# pa-2g.net
KiCad netlist of a schematic drawn in Altium Designer
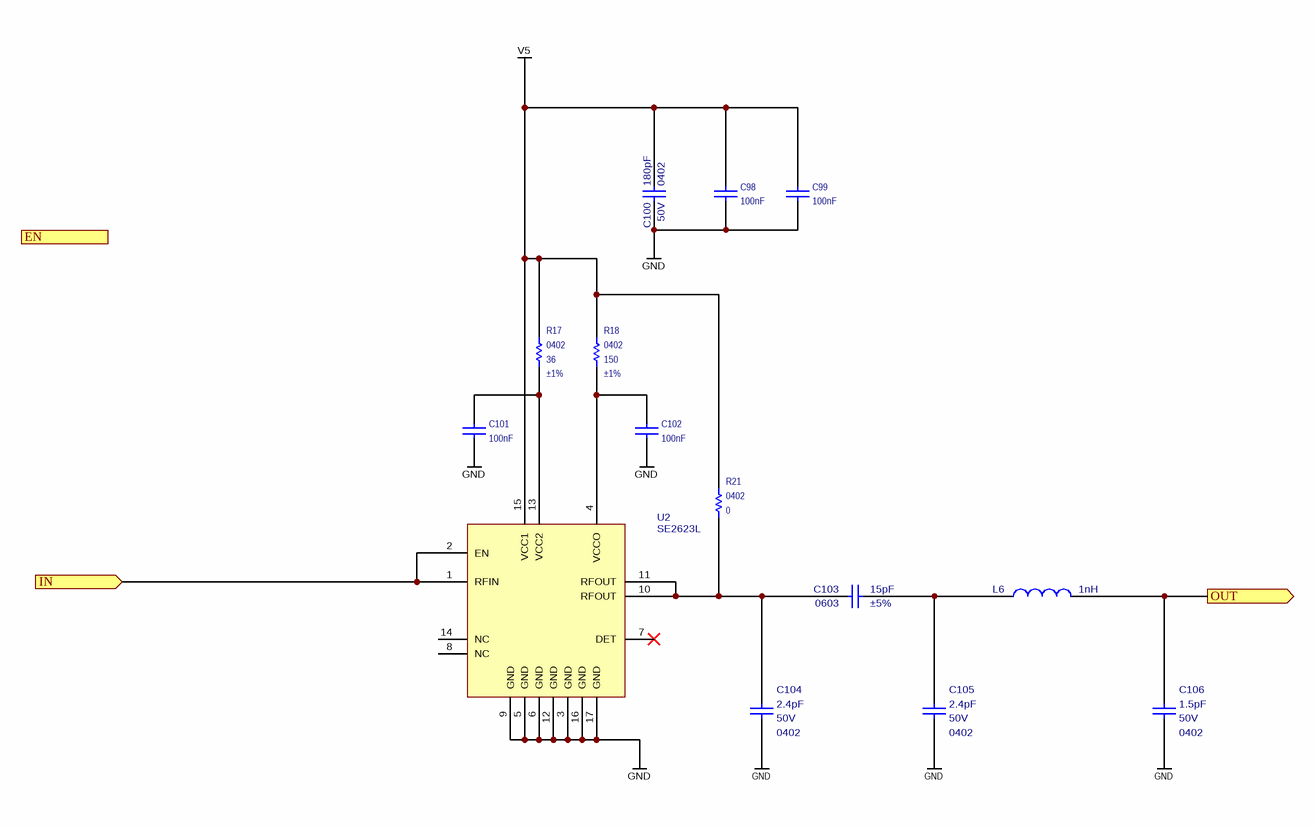
[diagram p0: pa-2g.SchDoc]

(export (version "E")
  (design (tool "Eeschema 10.0.6"))
  (components
    (comp (ref "C98")
      (value "100nF")
      (footprint "CAPC100X50X55L25N")
      (description "Ceramic Capacitor 100nF ±10% 16V X7R 0402")
      (fields (field (name "VOLTAGE") "16V") (field (name "MANUFACTURER") "Murata"))
      (libsource (lib "Graviton") (part "CAP 0402"))
    )
    (comp (ref "C99")
      (value "100nF")
      (footprint "CAPC100X50X55L25N")
      (description "Ceramic Capacitor 100nF ±10% 16V X7R 0402")
      (fields (field (name "VOLTAGE") "16V") (field (name "MANUFACTURER") "Murata"))
      (libsource (lib "Graviton") (part "CAP 0402"))
    )
    (comp (ref "C100")
      (value "180pF")
      (footprint "CAPC160X80X90L20N")
      (description "Ceramic Capacitor 180pF ±5% 50V C0G 0402")
      (fields
        (field (name "MANUFACTURER") "Vishay")
        (field (name "TOLERANCE") "±5%")
        (field (name "PACKAGE") "0402")
        (field (name "VOLTAGE") "50V")
      )
      (libsource (lib "capacitors") (part "CAP"))
    )
    (comp (ref "C101")
      (value "100nF")
      (footprint "CAPC100X50X55L25N")
      (description "Ceramic Capacitor 100nF ±10% 16V X7R 0402")
      (fields (field (name "VOLTAGE") "16V") (field (name "MANUFACTURER") "Murata"))
      (libsource (lib "Graviton") (part "CAP 0402"))
    )
    (comp (ref "C102")
      (value "100nF")
      (footprint "CAPC100X50X55L25N")
      (description "Ceramic Capacitor 100nF ±10% 16V X7R 0402")
      (fields (field (name "VOLTAGE") "16V") (field (name "MANUFACTURER") "Murata"))
      (libsource (lib "Graviton") (part "CAP 0402"))
    )
    (comp (ref "C103")
      (value "15pF")
      (footprint "CAPC160X80X90L20N")
      (description "Ceramic Capacitor 15pF ±5% NP0 0603")
      (fields
        (field (name "MANUFACTURER") "Murata")
        (field (name "TOLERANCE") "±5%")
        (field (name "VOLTAGE") "50V")
        (field (name "PACKAGE") "0603")
      )
      (libsource (lib "generic") (part "CAP"))
    )
    (comp (ref "C104")
      (value "2.4pF")
      (footprint "CAPC100X50X55L25N")
      (description "Ceramic Capacitor 2.4pF ±0.1pF 50V C0G 0402")
      (fields
        (field (name "MANUFACTURER") "Vishay")
        (field (name "TOLERANCE") "±0.1pF")
        (field (name "PACKAGE") "0402")
        (field (name "VOLTAGE") "50V")
      )
      (libsource (lib "capacitors") (part "CAP"))
    )
    (comp (ref "C105")
      (value "2.4pF")
      (footprint "CAPC100X50X55L25N")
      (description "Ceramic Capacitor 2.4pF ±0.1pF 50V C0G 0402")
      (fields
        (field (name "MANUFACTURER") "Vishay")
        (field (name "TOLERANCE") "±0.1pF")
        (field (name "PACKAGE") "0402")
        (field (name "VOLTAGE") "50V")
      )
      (libsource (lib "capacitors") (part "CAP"))
    )
    (comp (ref "C106")
      (value "1.5pF")
      (footprint "CAPC100X50X55L25N")
      (description "Ceramic Capacitor 1.5pF ±0.1pF 50V C0G 0402")
      (fields
        (field (name "MANUFACTURER") "Vishay")
        (field (name "TOLERANCE") "±0.1pF")
        (field (name "PACKAGE") "0402")
        (field (name "VOLTAGE") "50V")
      )
      (libsource (lib "capacitors") (part "CAP"))
    )
    (comp (ref "L6")
      (value "1nH")
      (footprint "generic:INDC1005X55N")
      (description "Inductor 1nH ±0.3nH 1A")
      (fields (field (name "MANUFACTURER") "Murata") (field (name "Comment") "LQG15HS8N2H02D"))
      (libsource (lib "generic") (part "INDUCTOR"))
    )
    (comp (ref "R17")
      (value "36")
      (footprint "RESC1005X40N")
      (description "Thin Film Resistor 36 +/-1% SMD 0402")
      (fields
        (field (name "TOLERANCE") "±1%")
        (field (name "MANUFACTURER") "Panasoinc")
        (field (name "POWER") "0.063W")
        (field (name "PACKAGE") "0402")
      )
      (libsource (lib "generic") (part "RES"))
    )
    (comp (ref "R18")
      (value "150")
      (footprint "RESC1005X40N")
      (description "Thin Film Resistor 150 +/-1% SMD 0402")
      (fields
        (field (name "TOLERANCE") "±1%")
        (field (name "MANUFACTURER") "Panasoinc")
        (field (name "POWER") "0.063W")
        (field (name "PACKAGE") "0402")
      )
      (libsource (lib "generic") (part "RES"))
    )
    (comp (ref "R21")
      (value "0")
      (footprint "RESC1005X40N")
      (description "Thin Film Resistor 0 +/-1% SMD 0402")
      (fields
        (field (name "MANUFACTURER") "Panasoinc")
        (field (name "POWER") "0.063W")
        (field (name "PACKAGE") "0402")
      )
      (libsource (lib "generic") (part "RES"))
    )
    (comp (ref "U2")
      (value "SE2623L")
      (footprint "SE2623L")
      (description "2.4 GHz, 33dB Power Amplifier")
      (libsource (lib "skyworks") (part "SE2623L"))
    )
  )
  (nets
    (net (code "2") (name "/IN") (class "Default")
      (node (ref "U2") (pin "1") (pinfunction "RFIN_1") (pintype "passive"))
      (node (ref "U2") (pin "2") (pinfunction "EN_2") (pintype "passive"))
    )
    (net (code "3") (name "/OUT") (class "Default")
      (node (ref "C106") (pin "1") (pinfunction "1_1") (pintype "passive"))
      (node (ref "L6") (pin "2") (pinfunction "2_2") (pintype "passive"))
    )
    (net (code "4") (name "GND") (class "Default")
      (node (ref "C100") (pin "1") (pinfunction "1_1") (pintype "passive"))
      (node (ref "C101") (pin "1") (pinfunction "1_1") (pintype "passive"))
      (node (ref "C102") (pin "1") (pinfunction "1_1") (pintype "passive"))
      (node (ref "C104") (pin "2") (pinfunction "2_2") (pintype "passive"))
      (node (ref "C105") (pin "2") (pinfunction "2_2") (pintype "passive"))
      (node (ref "C106") (pin "2") (pinfunction "2_2") (pintype "passive"))
      (node (ref "C98") (pin "1") (pinfunction "1_1") (pintype "passive"))
      (node (ref "C99") (pin "1") (pinfunction "1_1") (pintype "passive"))
      (node (ref "U2") (pin "12") (pinfunction "GND_12") (pintype "passive"))
      (node (ref "U2") (pin "16") (pinfunction "GND_16") (pintype "passive"))
      (node (ref "U2") (pin "17") (pinfunction "GND_17") (pintype "passive"))
      (node (ref "U2") (pin "3") (pinfunction "GND_3") (pintype "passive"))
      (node (ref "U2") (pin "5") (pinfunction "GND_5") (pintype "passive"))
      (node (ref "U2") (pin "6") (pinfunction "GND_6") (pintype "passive"))
      (node (ref "U2") (pin "9") (pinfunction "GND_9") (pintype "passive"))
    )
    (net (code "5") (name "Net-(C103-Pad1)") (class "Default")
      (node (ref "C103") (pin "1") (pinfunction "1_1") (pintype "passive"))
      (node (ref "C104") (pin "1") (pinfunction "1_1") (pintype "passive"))
      (node (ref "R21") (pin "1") (pinfunction "1_1") (pintype "passive"))
      (node (ref "U2") (pin "10") (pinfunction "RFOUT_10") (pintype "passive"))
      (node (ref "U2") (pin "11") (pinfunction "RFOUT_11") (pintype "passive"))
    )
    (net (code "6") (name "Net-(C103-Pad2)") (class "Default")
      (node (ref "C103") (pin "2") (pinfunction "2_2") (pintype "passive"))
      (node (ref "C105") (pin "1") (pinfunction "1_1") (pintype "passive"))
      (node (ref "L6") (pin "1") (pinfunction "1_1") (pintype "passive"))
    )
    (net (code "7") (name "Net-(U2-VCC2)") (class "Default")
      (node (ref "C101") (pin "2") (pinfunction "2_2") (pintype "passive"))
      (node (ref "R17") (pin "1") (pinfunction "1_1") (pintype "passive"))
      (node (ref "U2") (pin "13") (pinfunction "VCC2_13") (pintype "passive"))
    )
    (net (code "8") (name "Net-(U2-VCCO)") (class "Default")
      (node (ref "C102") (pin "2") (pinfunction "2_2") (pintype "passive"))
      (node (ref "R18") (pin "1") (pinfunction "1_1") (pintype "passive"))
      (node (ref "U2") (pin "4") (pinfunction "VCCO_4") (pintype "passive"))
    )
    (net (code "9") (name "V5") (class "Default")
      (node (ref "C100") (pin "2") (pinfunction "2_2") (pintype "passive"))
      (node (ref "C98") (pin "2") (pinfunction "2_2") (pintype "passive"))
      (node (ref "C99") (pin "2") (pinfunction "2_2") (pintype "passive"))
      (node (ref "R17") (pin "2") (pinfunction "2_2") (pintype "passive"))
      (node (ref "R18") (pin "2") (pinfunction "2_2") (pintype "passive"))
      (node (ref "R21") (pin "2") (pinfunction "2_2") (pintype "passive"))
      (node (ref "U2") (pin "15") (pinfunction "VCC1_15") (pintype "passive"))
    )
    (net (code "10") (name "unconnected-(U2-DET-Pad7)") (class "Default")
      (node (ref "U2") (pin "7") (pinfunction "DET_7") (pintype "passive+no_connect"))
    )
    (net (code "11") (name "unconnected-(U2-NC-Pad8)") (class "Default")
      (node (ref "U2") (pin "8") (pinfunction "NC_8") (pintype "passive"))
    )
    (net (code "12") (name "unconnected-(U2-NC-Pad14)") (class "Default")
      (node (ref "U2") (pin "14") (pinfunction "NC_14") (pintype "passive"))
    )
  )
)
